# ESP12E_Si7021_meteostation.net
KiCad netlist of a schematic drawn in EAGLE
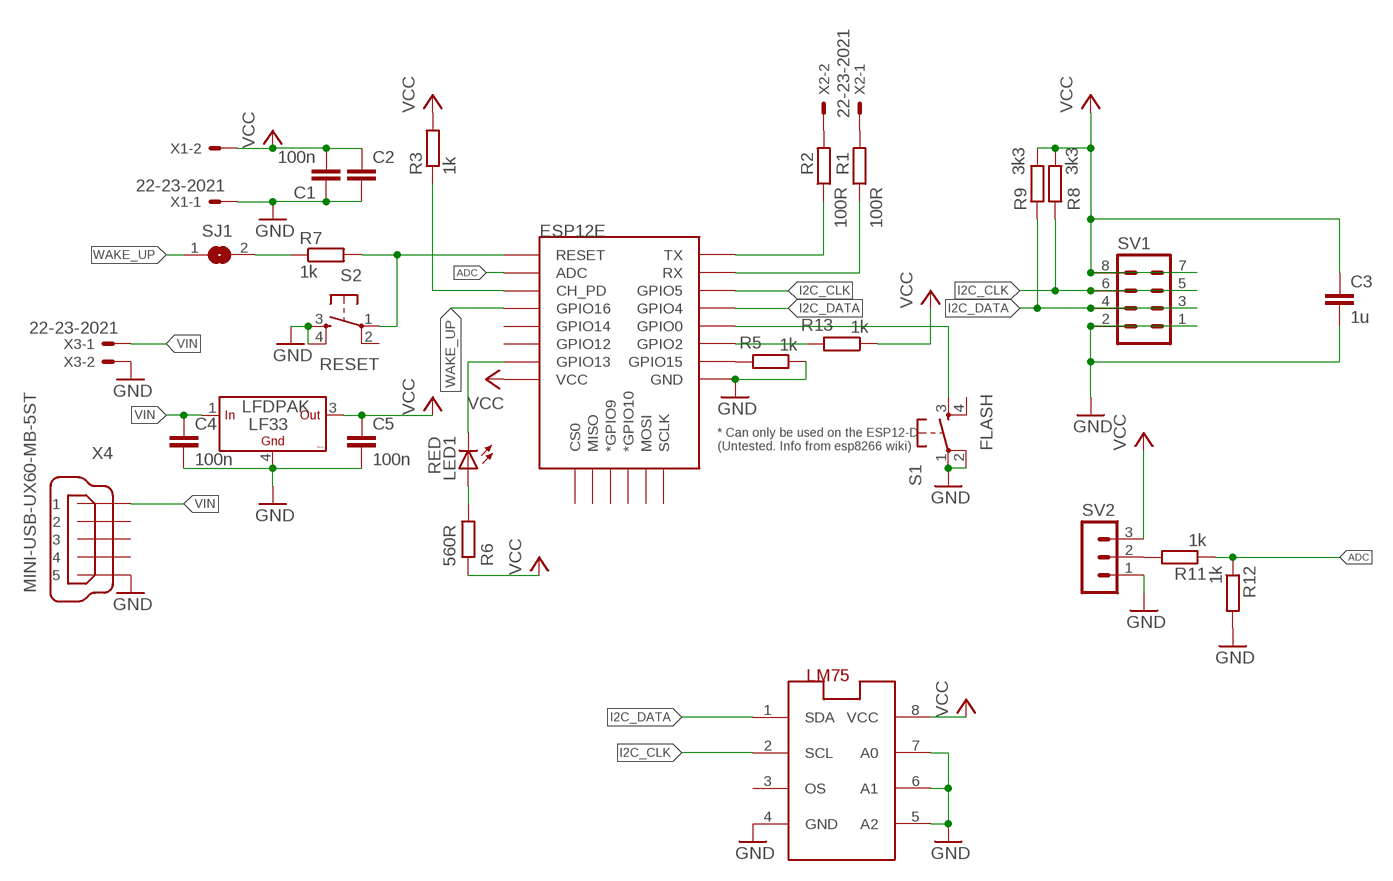
[diagram p0: schematic, sheet 1]

(export (version "E")
  (design (tool "Eeschema 10.0.6"))
  (components
    (comp (ref "C1")
      (value "100n")
      (footprint "eagle-import:C3225")
      (libsource (lib "eagle-import") (part "C-EUC3225"))
    )
    (comp (ref "C2")
      (value "C-EUC1206")
      (footprint "eagle-import:C1206")
      (libsource (lib "eagle-import") (part "C-EUC1206"))
    )
    (comp (ref "C3")
      (value "1u")
      (footprint "eagle-import:C1206")
      (libsource (lib "eagle-import") (part "C-EUC1206"))
    )
    (comp (ref "C4")
      (value "100n")
      (footprint "eagle-import:C1206")
      (libsource (lib "eagle-import") (part "C-EUC1206"))
    )
    (comp (ref "C5")
      (value "100n")
      (footprint "eagle-import:C1206")
      (libsource (lib "eagle-import") (part "C-EUC1206"))
    )
    (comp (ref "ESP12E")
      (value "ESP12ESMD")
      (footprint "eagle-import:ESP12E-SMD")
      (libsource (lib "eagle-import") (part "ESP12ESMD"))
    )
    (comp (ref "LED1")
      (value "RED")
      (footprint "eagle-import:CHIPLED_0603")
      (libsource (lib "eagle-import") (part "LEDCHIPLED_0603"))
    )
    (comp (ref "LF33")
      (value "LFDPAK")
      (footprint "eagle-import:DPAK")
      (libsource (lib "eagle-import") (part "LF??CDPAK"))
    )
    (comp (ref "LM75")
      (value "LM75_ICN")
      (footprint "eagle-import:SO8_LM75")
      (libsource (lib "eagle-import") (part "LM75_ICN"))
    )
    (comp (ref "R1")
      (value "100R")
      (footprint "eagle-import:R0805")
      (libsource (lib "eagle-import") (part "R-EU_R0805"))
    )
    (comp (ref "R2")
      (value "100R")
      (footprint "eagle-import:R0805")
      (libsource (lib "eagle-import") (part "R-EU_R0805"))
    )
    (comp (ref "R3")
      (value "1k")
      (footprint "eagle-import:R1206")
      (libsource (lib "eagle-import") (part "R-EU_R1206"))
    )
    (comp (ref "R5")
      (value "1k")
      (footprint "eagle-import:R0805")
      (libsource (lib "eagle-import") (part "R-EU_R0805"))
    )
    (comp (ref "R6")
      (value "560R")
      (footprint "eagle-import:R0805")
      (libsource (lib "eagle-import") (part "R-EU_R0805"))
    )
    (comp (ref "R7")
      (value "1k")
      (footprint "eagle-import:R0805")
      (libsource (lib "eagle-import") (part "R-EU_R0805"))
    )
    (comp (ref "R8")
      (value "3k3")
      (footprint "eagle-import:R0805")
      (libsource (lib "eagle-import") (part "R-EU_R0805"))
    )
    (comp (ref "R9")
      (value "3k3")
      (footprint "eagle-import:R0805")
      (libsource (lib "eagle-import") (part "R-EU_R0805"))
    )
    (comp (ref "R11")
      (value "1k")
      (footprint "eagle-import:M0805")
      (libsource (lib "eagle-import") (part "R-EU_M0805"))
    )
    (comp (ref "R12")
      (value "1k")
      (footprint "eagle-import:M0805")
      (libsource (lib "eagle-import") (part "R-EU_M0805"))
    )
    (comp (ref "R13")
      (value "1k")
      (footprint "eagle-import:R0805")
      (libsource (lib "eagle-import") (part "R-EU_R0805"))
    )
    (comp (ref "S1")
      (value "FLASH")
      (footprint "eagle-import:TACTILE-PTH")
      (libsource (lib "eagle-import") (part "TAC_SWITCHPTH"))
    )
    (comp (ref "S2")
      (value "RESET")
      (footprint "eagle-import:TACTILE-PTH")
      (libsource (lib "eagle-import") (part "TAC_SWITCHPTH"))
    )
    (comp (ref "SJ1") (value "SJ") (footprint "eagle-import:SJ") (libsource (lib "eagle-import") (part "SJ")))
    (comp (ref "SV1")
      (value "MA04-2")
      (footprint "eagle-import:MA04-2")
      (libsource (lib "eagle-import") (part "MA04-2"))
    )
    (comp (ref "SV2")
      (value "MA03-1")
      (footprint "eagle-import:MA03-1")
      (libsource (lib "eagle-import") (part "MA03-1"))
    )
    (comp (ref "X1")
      (value "22-23-2021")
      (footprint "eagle-import:22-23-2021")
      (fields (field (name "MF") "MOLEX"))
      (libsource (lib "eagle-import") (part "22-23-2021"))
    )
    (comp (ref "X2")
      (value "22-23-2021")
      (footprint "eagle-import:22-23-2021")
      (fields (field (name "MF") "MOLEX"))
      (libsource (lib "eagle-import") (part "22-23-2021"))
    )
    (comp (ref "X3")
      (value "22-23-2021")
      (footprint "eagle-import:22-23-2021")
      (fields (field (name "MF") "MOLEX"))
      (libsource (lib "eagle-import") (part "22-23-2021"))
    )
    (comp (ref "X4")
      (value "MINI-USB-UX60-MB-5ST")
      (footprint "eagle-import:UX60-MB-5ST")
      (libsource (lib "eagle-import") (part "MINI-USB-UX60-MB-5ST"))
    )
  )
  (nets
    (net (code "1") (name "ADC") (class "Default")
      (node (ref "ESP12E") (pin "ADC") (pinfunction "ADC_ADC") (pintype "bidirectional"))
      (node (ref "R11") (pin "1") (pinfunction "1_1") (pintype "passive"))
      (node (ref "R12") (pin "1") (pinfunction "1_1") (pintype "passive"))
    )
    (net (code "2") (name "GND") (class "Default")
      (node (ref "C1") (pin "1") (pinfunction "1_1") (pintype "passive"))
      (node (ref "C2") (pin "2") (pinfunction "2_2") (pintype "passive"))
      (node (ref "C3") (pin "2") (pinfunction "2_2") (pintype "passive"))
      (node (ref "C4") (pin "2") (pinfunction "2_2") (pintype "passive"))
      (node (ref "C5") (pin "2") (pinfunction "2_2") (pintype "passive"))
      (node (ref "ESP12E") (pin "GND") (pinfunction "GND_GND") (pintype "bidirectional"))
      (node (ref "LF33") (pin "4") (pinfunction "GND_4") (pintype "passive"))
      (node (ref "LM75") (pin "4") (pinfunction "GND_4") (pintype "power_in"))
      (node (ref "LM75") (pin "5") (pinfunction "A2_5") (pintype "input"))
      (node (ref "LM75") (pin "6") (pinfunction "A1_6") (pintype "input"))
      (node (ref "LM75") (pin "7") (pinfunction "A0_7") (pintype "input"))
      (node (ref "R12") (pin "2") (pinfunction "2_2") (pintype "passive"))
      (node (ref "R5") (pin "1") (pinfunction "1_1") (pintype "passive"))
      (node (ref "S1") (pin "1") (pinfunction "1_1") (pintype "passive"))
      (node (ref "S1") (pin "2") (pinfunction "2_2") (pintype "passive"))
      (node (ref "S2") (pin "3") (pinfunction "3_3") (pintype "passive"))
      (node (ref "S2") (pin "4") (pinfunction "4_4") (pintype "passive"))
      (node (ref "SV1") (pin "1") (pinfunction "1_1") (pintype "passive"))
      (node (ref "SV1") (pin "2") (pinfunction "2_2") (pintype "passive"))
      (node (ref "SV2") (pin "1") (pinfunction "1_1") (pintype "passive"))
      (node (ref "X1") (pin "1") (pinfunction "S_1") (pintype "passive"))
      (node (ref "X3") (pin "2") (pinfunction "S_2") (pintype "passive"))
      (node (ref "X4") (pin "5") (pinfunction "5_5") (pintype "input"))
    )
    (net (code "3") (name "I2C_CLK") (class "Default")
      (node (ref "ESP12E") (pin "GPIO5") (pinfunction "GPIO5_GPIO5") (pintype "bidirectional"))
      (node (ref "LM75") (pin "2") (pinfunction "SCL_2") (pintype "bidirectional"))
      (node (ref "R8") (pin "1") (pinfunction "1_1") (pintype "passive"))
      (node (ref "SV1") (pin "5") (pinfunction "5_5") (pintype "passive"))
      (node (ref "SV1") (pin "6") (pinfunction "6_6") (pintype "passive"))
    )
    (net (code "4") (name "I2C_DATA") (class "Default")
      (node (ref "ESP12E") (pin "GPIO4") (pinfunction "GPIO4_GPIO4") (pintype "bidirectional"))
      (node (ref "LM75") (pin "1") (pinfunction "SDA_1") (pintype "bidirectional"))
      (node (ref "R9") (pin "1") (pinfunction "1_1") (pintype "passive"))
      (node (ref "SV1") (pin "3") (pinfunction "3_3") (pintype "passive"))
      (node (ref "SV1") (pin "4") (pinfunction "4_4") (pintype "passive"))
    )
    (net (code "5") (name "Net-(ESP12E-PadCH_PD)") (class "Default")
      (node (ref "ESP12E") (pin "CH_PD") (pinfunction "CH_PD_CH_PD") (pintype "bidirectional"))
      (node (ref "R3") (pin "1") (pinfunction "1_1") (pintype "passive"))
    )
    (net (code "6") (name "Net-(ESP12E-PadGPIO0)") (class "Default")
      (node (ref "ESP12E") (pin "GPIO0") (pinfunction "GPIO0_GPIO0") (pintype "bidirectional"))
      (node (ref "S1") (pin "3") (pinfunction "3_3") (pintype "passive"))
    )
    (net (code "7") (name "Net-(ESP12E-PadGPIO2)") (class "Default")
      (node (ref "ESP12E") (pin "GPIO2") (pinfunction "GPIO2_GPIO2") (pintype "bidirectional"))
      (node (ref "R13") (pin "2") (pinfunction "2_2") (pintype "passive"))
    )
    (net (code "8") (name "Net-(ESP12E-PadGPIO13)") (class "Default")
      (node (ref "ESP12E") (pin "GPIO13") (pinfunction "GPIO13_GPIO13") (pintype "bidirectional"))
      (node (ref "LED1") (pin "C") (pinfunction "C_C") (pintype "passive"))
    )
    (net (code "9") (name "Net-(ESP12E-PadGPIO15)") (class "Default")
      (node (ref "ESP12E") (pin "GPIO15") (pinfunction "GPIO15_GPIO15") (pintype "bidirectional"))
      (node (ref "R5") (pin "2") (pinfunction "2_2") (pintype "passive"))
    )
    (net (code "10") (name "Net-(ESP12E-PadRESET)") (class "Default")
      (node (ref "ESP12E") (pin "RESET") (pinfunction "RESET_RESET") (pintype "bidirectional"))
      (node (ref "R7") (pin "2") (pinfunction "2_2") (pintype "passive"))
      (node (ref "S2") (pin "1") (pinfunction "1_1") (pintype "passive"))
    )
    (net (code "11") (name "Net-(ESP12E-RX)") (class "Default")
      (node (ref "ESP12E") (pin "RXD0") (pinfunction "RX_RXD0") (pintype "bidirectional"))
      (node (ref "R1") (pin "1") (pinfunction "1_1") (pintype "passive"))
    )
    (net (code "12") (name "Net-(ESP12E-TX)") (class "Default")
      (node (ref "ESP12E") (pin "TXD0") (pinfunction "TX_TXD0") (pintype "bidirectional"))
      (node (ref "R2") (pin "1") (pinfunction "1_1") (pintype "passive"))
    )
    (net (code "13") (name "Net-(LED1-PadA)") (class "Default")
      (node (ref "LED1") (pin "A") (pinfunction "A_A") (pintype "passive"))
      (node (ref "R6") (pin "2") (pinfunction "2_2") (pintype "passive"))
    )
    (net (code "14") (name "Net-(R7-Pad1)") (class "Default")
      (node (ref "R7") (pin "1") (pinfunction "1_1") (pintype "passive"))
      (node (ref "SJ1") (pin "2") (pinfunction "2_2") (pintype "passive"))
    )
    (net (code "15") (name "Net-(R11-Pad2)") (class "Default")
      (node (ref "R11") (pin "2") (pinfunction "2_2") (pintype "passive"))
      (node (ref "SV2") (pin "2") (pinfunction "2_2") (pintype "passive"))
    )
    (net (code "16") (name "Net-(X2A-S)") (class "Default")
      (node (ref "R1") (pin "2") (pinfunction "2_2") (pintype "passive"))
      (node (ref "X2") (pin "1") (pinfunction "S_1") (pintype "passive"))
    )
    (net (code "17") (name "Net-(X2B-S)") (class "Default")
      (node (ref "R2") (pin "2") (pinfunction "2_2") (pintype "passive"))
      (node (ref "X2") (pin "2") (pinfunction "S_2") (pintype "passive"))
    )
    (net (code "18") (name "VCC") (class "Default")
      (node (ref "C1") (pin "2") (pinfunction "2_2") (pintype "passive"))
      (node (ref "C2") (pin "1") (pinfunction "1_1") (pintype "passive"))
      (node (ref "C3") (pin "1") (pinfunction "1_1") (pintype "passive"))
      (node (ref "C5") (pin "1") (pinfunction "1_1") (pintype "passive"))
      (node (ref "ESP12E") (pin "VCC") (pinfunction "VCC_VCC") (pintype "bidirectional"))
      (node (ref "LF33") (pin "3") (pinfunction "OUT_3") (pintype "passive"))
      (node (ref "LM75") (pin "8") (pinfunction "VCC_8") (pintype "power_in"))
      (node (ref "R13") (pin "1") (pinfunction "1_1") (pintype "passive"))
      (node (ref "R3") (pin "2") (pinfunction "2_2") (pintype "passive"))
      (node (ref "R6") (pin "1") (pinfunction "1_1") (pintype "passive"))
      (node (ref "R8") (pin "2") (pinfunction "2_2") (pintype "passive"))
      (node (ref "R9") (pin "2") (pinfunction "2_2") (pintype "passive"))
      (node (ref "SV1") (pin "7") (pinfunction "7_7") (pintype "passive"))
      (node (ref "SV1") (pin "8") (pinfunction "8_8") (pintype "passive"))
      (node (ref "SV2") (pin "3") (pinfunction "3_3") (pintype "passive"))
      (node (ref "X1") (pin "2") (pinfunction "S_2") (pintype "passive"))
    )
    (net (code "19") (name "VIN") (class "Default")
      (node (ref "C4") (pin "1") (pinfunction "1_1") (pintype "passive"))
      (node (ref "LF33") (pin "1") (pinfunction "IN_1") (pintype "passive"))
      (node (ref "X3") (pin "1") (pinfunction "S_1") (pintype "passive"))
      (node (ref "X4") (pin "1") (pinfunction "1_1") (pintype "input"))
    )
    (net (code "20") (name "WAKE_UP") (class "Default")
      (node (ref "ESP12E") (pin "GPIO16") (pinfunction "GPIO16_GPIO16") (pintype "bidirectional"))
      (node (ref "SJ1") (pin "1") (pinfunction "1_1") (pintype "passive"))
    )
    (net (code "21") (name "unconnected-(ESP12E-*GPIO9-PadGPIO9)") (class "Default")
      (node (ref "ESP12E") (pin "GPIO9") (pinfunction "*GPIO9_GPIO9") (pintype "bidirectional"))
    )
    (net (code "22") (name "unconnected-(ESP12E-*GPIO10-PadGPIO10)") (class "Default")
      (node (ref "ESP12E") (pin "GPIO10") (pinfunction "*GPIO10_GPIO10") (pintype "bidirectional"))
    )
    (net (code "23") (name "unconnected-(ESP12E-PadCS0)") (class "Default")
      (node (ref "ESP12E") (pin "CS0") (pinfunction "CS0_CS0") (pintype "bidirectional"))
    )
    (net (code "24") (name "unconnected-(ESP12E-PadGPIO12)") (class "Default")
      (node (ref "ESP12E") (pin "GPIO12") (pinfunction "GPIO12_GPIO12") (pintype "bidirectional"))
    )
    (net (code "25") (name "unconnected-(ESP12E-PadGPIO14)") (class "Default")
      (node (ref "ESP12E") (pin "GPIO14") (pinfunction "GPIO14_GPIO14") (pintype "bidirectional"))
    )
    (net (code "26") (name "unconnected-(ESP12E-PadMISO)") (class "Default")
      (node (ref "ESP12E") (pin "MISO") (pinfunction "MISO_MISO") (pintype "bidirectional"))
    )
    (net (code "27") (name "unconnected-(ESP12E-PadMOSI)") (class "Default")
      (node (ref "ESP12E") (pin "MOSI") (pinfunction "MOSI_MOSI") (pintype "bidirectional"))
    )
    (net (code "28") (name "unconnected-(ESP12E-PadSCLK)") (class "Default")
      (node (ref "ESP12E") (pin "SCLK") (pinfunction "SCLK_SCLK") (pintype "bidirectional"))
    )
    (net (code "29") (name "unconnected-(LM75-OS-Pad3)") (class "Default")
      (node (ref "LM75") (pin "3") (pinfunction "OS_3") (pintype "output"))
    )
    (net (code "30") (name "unconnected-(S1-Pad4)") (class "Default")
      (node (ref "S1") (pin "4") (pinfunction "4_4") (pintype "passive"))
    )
    (net (code "31") (name "unconnected-(S2-Pad2)") (class "Default")
      (node (ref "S2") (pin "2") (pinfunction "2_2") (pintype "passive"))
    )
    (net (code "32") (name "unconnected-(X4-Pad2)") (class "Default")
      (node (ref "X4") (pin "2") (pinfunction "2_2") (pintype "input"))
    )
    (net (code "33") (name "unconnected-(X4-Pad3)") (class "Default")
      (node (ref "X4") (pin "3") (pinfunction "3_3") (pintype "input"))
    )
    (net (code "34") (name "unconnected-(X4-Pad4)") (class "Default")
      (node (ref "X4") (pin "4") (pinfunction "4_4") (pintype "input"))
    )
  )
)
